# v1.net
KiCad netlist of a schematic drawn in EAGLE
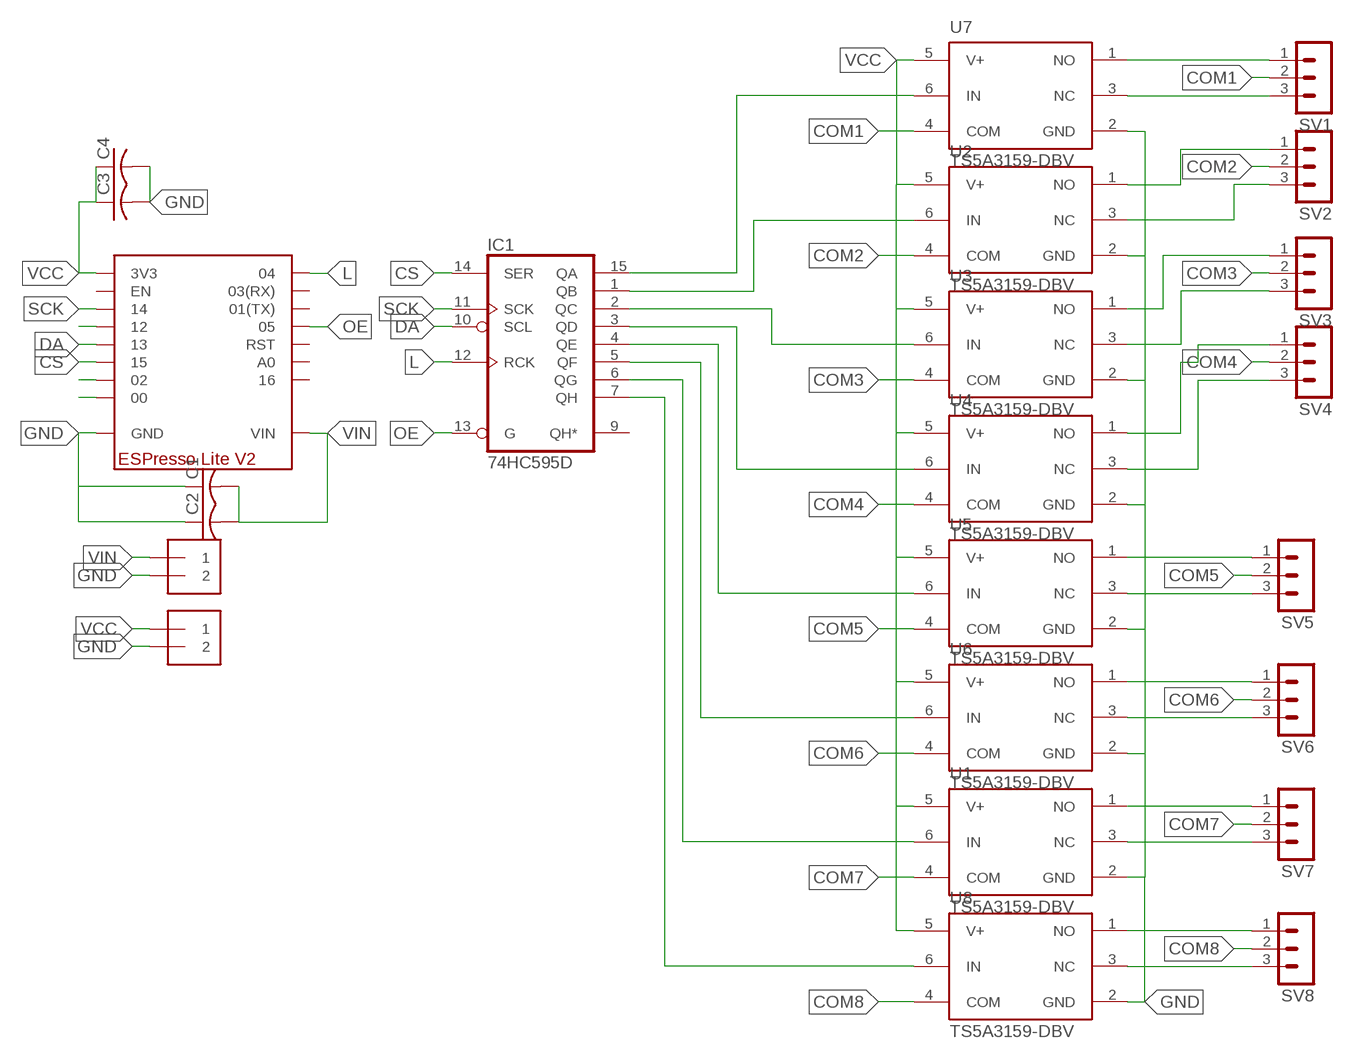
[diagram p0: schematic, sheet 1]

(export (version "E")
  (design (tool "Eeschema 10.0.6"))
  (components
    (comp (ref "C1")
      (value "C-USC0805")
      (footprint "eagle-import:C0805")
      (libsource (lib "eagle-import") (part "C-USC0805"))
    )
    (comp (ref "C2")
      (value "C-USC0805")
      (footprint "eagle-import:C0805")
      (libsource (lib "eagle-import") (part "C-USC0805"))
    )
    (comp (ref "C3")
      (value "C-USC0805")
      (footprint "eagle-import:C0805")
      (libsource (lib "eagle-import") (part "C-USC0805"))
    )
    (comp (ref "C4")
      (value "C-USC0805")
      (footprint "eagle-import:C0805")
      (libsource (lib "eagle-import") (part "C-USC0805"))
    )
    (comp (ref "IC1")
      (value "74HC595D")
      (footprint "eagle-import:SO16")
      (libsource (lib "eagle-import") (part "74595DHC"))
    )
    (comp (ref "J1")
      (value "1X2-3.5MM")
      (footprint "eagle-import:1X2-3.5MM")
      (libsource (lib "eagle-import") (part "1X2-3.5MM"))
    )
    (comp (ref "J2")
      (value "1X2-3.5MM")
      (footprint "eagle-import:1X2-3.5MM")
      (libsource (lib "eagle-import") (part "1X2-3.5MM"))
    )
    (comp (ref "SV1")
      (value "MA03-1")
      (footprint "eagle-import:MA03-1")
      (libsource (lib "eagle-import") (part "MA03-1"))
    )
    (comp (ref "SV2")
      (value "MA03-1")
      (footprint "eagle-import:MA03-1")
      (libsource (lib "eagle-import") (part "MA03-1"))
    )
    (comp (ref "SV3")
      (value "MA03-1")
      (footprint "eagle-import:MA03-1")
      (libsource (lib "eagle-import") (part "MA03-1"))
    )
    (comp (ref "SV4")
      (value "MA03-1")
      (footprint "eagle-import:MA03-1")
      (libsource (lib "eagle-import") (part "MA03-1"))
    )
    (comp (ref "SV5")
      (value "MA03-1")
      (footprint "eagle-import:MA03-1")
      (libsource (lib "eagle-import") (part "MA03-1"))
    )
    (comp (ref "SV6")
      (value "MA03-1")
      (footprint "eagle-import:MA03-1")
      (libsource (lib "eagle-import") (part "MA03-1"))
    )
    (comp (ref "SV7")
      (value "MA03-1")
      (footprint "eagle-import:MA03-1")
      (libsource (lib "eagle-import") (part "MA03-1"))
    )
    (comp (ref "SV8")
      (value "MA03-1")
      (footprint "eagle-import:MA03-1")
      (libsource (lib "eagle-import") (part "MA03-1"))
    )
    (comp (ref "U$1")
      (value "ESPRESSO-LITE-V2")
      (footprint "eagle-import:ESPRESSO-LITE-V2")
      (libsource (lib "eagle-import") (part "ESPRESSO-LITE-V2"))
    )
    (comp (ref "U1")
      (value "TS5A3159-DBV")
      (footprint "eagle-import:SOT23-6L")
      (libsource (lib "eagle-import") (part "TS5A3159-DBV"))
    )
    (comp (ref "U2")
      (value "TS5A3159-DBV")
      (footprint "eagle-import:SOT23-6L")
      (libsource (lib "eagle-import") (part "TS5A3159-DBV"))
    )
    (comp (ref "U3")
      (value "TS5A3159-DBV")
      (footprint "eagle-import:SOT23-6L")
      (libsource (lib "eagle-import") (part "TS5A3159-DBV"))
    )
    (comp (ref "U4")
      (value "TS5A3159-DBV")
      (footprint "eagle-import:SOT23-6L")
      (libsource (lib "eagle-import") (part "TS5A3159-DBV"))
    )
    (comp (ref "U5")
      (value "TS5A3159-DBV")
      (footprint "eagle-import:SOT23-6L")
      (libsource (lib "eagle-import") (part "TS5A3159-DBV"))
    )
    (comp (ref "U6")
      (value "TS5A3159-DBV")
      (footprint "eagle-import:SOT23-6L")
      (libsource (lib "eagle-import") (part "TS5A3159-DBV"))
    )
    (comp (ref "U7")
      (value "TS5A3159-DBV")
      (footprint "eagle-import:SOT23-6L")
      (libsource (lib "eagle-import") (part "TS5A3159-DBV"))
    )
    (comp (ref "U8")
      (value "TS5A3159-DBV")
      (footprint "eagle-import:SOT23-6L")
      (libsource (lib "eagle-import") (part "TS5A3159-DBV"))
    )
  )
  (nets
    (net (code "1") (name "COM1") (class "Default")
      (node (ref "SV1") (pin "2") (pinfunction "2_2") (pintype "passive"))
      (node (ref "U7") (pin "4") (pinfunction "COM_4") (pintype "bidirectional"))
    )
    (net (code "2") (name "COM2") (class "Default")
      (node (ref "SV2") (pin "2") (pinfunction "2_2") (pintype "passive"))
      (node (ref "U2") (pin "4") (pinfunction "COM_4") (pintype "bidirectional"))
    )
    (net (code "3") (name "COM3") (class "Default")
      (node (ref "SV3") (pin "2") (pinfunction "2_2") (pintype "passive"))
      (node (ref "U3") (pin "4") (pinfunction "COM_4") (pintype "bidirectional"))
    )
    (net (code "4") (name "COM4") (class "Default")
      (node (ref "SV4") (pin "2") (pinfunction "2_2") (pintype "passive"))
      (node (ref "U4") (pin "4") (pinfunction "COM_4") (pintype "bidirectional"))
    )
    (net (code "5") (name "COM5") (class "Default")
      (node (ref "SV5") (pin "2") (pinfunction "2_2") (pintype "passive"))
      (node (ref "U5") (pin "4") (pinfunction "COM_4") (pintype "bidirectional"))
    )
    (net (code "6") (name "COM6") (class "Default")
      (node (ref "SV6") (pin "2") (pinfunction "2_2") (pintype "passive"))
      (node (ref "U6") (pin "4") (pinfunction "COM_4") (pintype "bidirectional"))
    )
    (net (code "7") (name "COM7") (class "Default")
      (node (ref "SV7") (pin "2") (pinfunction "2_2") (pintype "passive"))
      (node (ref "U1") (pin "4") (pinfunction "COM_4") (pintype "bidirectional"))
    )
    (net (code "8") (name "COM8") (class "Default")
      (node (ref "SV8") (pin "2") (pinfunction "2_2") (pintype "passive"))
      (node (ref "U8") (pin "4") (pinfunction "COM_4") (pintype "bidirectional"))
    )
    (net (code "9") (name "CS") (class "Default")
      (node (ref "IC1") (pin "14") (pinfunction "SER_14") (pintype "input"))
      (node (ref "U$1") (pin "15") (pinfunction "15_15") (pintype "bidirectional"))
    )
    (net (code "10") (name "DA") (class "Default")
      (node (ref "IC1") (pin "10") (pinfunction "SCL_10") (pintype "input"))
      (node (ref "U$1") (pin "13") (pinfunction "13_13") (pintype "bidirectional"))
    )
    (net (code "11") (name "GND") (class "Default")
      (node (ref "C1") (pin "1") (pinfunction "1_1") (pintype "passive"))
      (node (ref "C2") (pin "1") (pinfunction "1_1") (pintype "passive"))
      (node (ref "C3") (pin "2") (pinfunction "2_2") (pintype "passive"))
      (node (ref "C4") (pin "2") (pinfunction "2_2") (pintype "passive"))
      (node (ref "J1") (pin "2") (pinfunction "2_2") (pintype "passive"))
      (node (ref "J2") (pin "2") (pinfunction "2_2") (pintype "passive"))
      (node (ref "U$1") (pin "GND1") (pinfunction "GND_GND1") (pintype "bidirectional"))
      (node (ref "U$1") (pin "GND2") (pinfunction "GND_GND2") (pintype "bidirectional"))
      (node (ref "U$1") (pin "GND3") (pinfunction "GND_GND3") (pintype "bidirectional"))
      (node (ref "U1") (pin "2") (pinfunction "GND_2") (pintype "power_in"))
      (node (ref "U2") (pin "2") (pinfunction "GND_2") (pintype "power_in"))
      (node (ref "U3") (pin "2") (pinfunction "GND_2") (pintype "power_in"))
      (node (ref "U4") (pin "2") (pinfunction "GND_2") (pintype "power_in"))
      (node (ref "U5") (pin "2") (pinfunction "GND_2") (pintype "power_in"))
      (node (ref "U6") (pin "2") (pinfunction "GND_2") (pintype "power_in"))
      (node (ref "U7") (pin "2") (pinfunction "GND_2") (pintype "power_in"))
      (node (ref "U8") (pin "2") (pinfunction "GND_2") (pintype "power_in"))
    )
    (net (code "12") (name "L") (class "Default")
      (node (ref "IC1") (pin "12") (pinfunction "RCK_12") (pintype "input"))
      (node (ref "U$1") (pin "04") (pinfunction "04_04") (pintype "bidirectional"))
    )
    (net (code "13") (name "Net-(IC1A-QA)") (class "Default")
      (node (ref "IC1") (pin "15") (pinfunction "QA_15") (pintype "tri_state"))
      (node (ref "U7") (pin "6") (pinfunction "IN_6") (pintype "input"))
    )
    (net (code "14") (name "Net-(IC1A-QB)") (class "Default")
      (node (ref "IC1") (pin "1") (pinfunction "QB_1") (pintype "tri_state"))
      (node (ref "U2") (pin "6") (pinfunction "IN_6") (pintype "input"))
    )
    (net (code "15") (name "Net-(IC1A-QC)") (class "Default")
      (node (ref "IC1") (pin "2") (pinfunction "QC_2") (pintype "tri_state"))
      (node (ref "U3") (pin "6") (pinfunction "IN_6") (pintype "input"))
    )
    (net (code "16") (name "Net-(IC1A-QD)") (class "Default")
      (node (ref "IC1") (pin "3") (pinfunction "QD_3") (pintype "tri_state"))
      (node (ref "U4") (pin "6") (pinfunction "IN_6") (pintype "input"))
    )
    (net (code "17") (name "Net-(IC1A-QE)") (class "Default")
      (node (ref "IC1") (pin "4") (pinfunction "QE_4") (pintype "tri_state"))
      (node (ref "U5") (pin "6") (pinfunction "IN_6") (pintype "input"))
    )
    (net (code "18") (name "Net-(IC1A-QF)") (class "Default")
      (node (ref "IC1") (pin "5") (pinfunction "QF_5") (pintype "tri_state"))
      (node (ref "U6") (pin "6") (pinfunction "IN_6") (pintype "input"))
    )
    (net (code "19") (name "Net-(IC1A-QG)") (class "Default")
      (node (ref "IC1") (pin "6") (pinfunction "QG_6") (pintype "tri_state"))
      (node (ref "U1") (pin "6") (pinfunction "IN_6") (pintype "input"))
    )
    (net (code "20") (name "Net-(IC1A-QH)") (class "Default")
      (node (ref "IC1") (pin "7") (pinfunction "QH_7") (pintype "tri_state"))
      (node (ref "U8") (pin "6") (pinfunction "IN_6") (pintype "input"))
    )
    (net (code "21") (name "Net-(U1-NC)") (class "Default")
      (node (ref "SV7") (pin "3") (pinfunction "3_3") (pintype "passive"))
      (node (ref "U1") (pin "3") (pinfunction "NC_3") (pintype "bidirectional"))
    )
    (net (code "22") (name "Net-(U1-NO)") (class "Default")
      (node (ref "SV7") (pin "1") (pinfunction "1_1") (pintype "passive"))
      (node (ref "U1") (pin "1") (pinfunction "NO_1") (pintype "bidirectional"))
    )
    (net (code "23") (name "Net-(U2-NC)") (class "Default")
      (node (ref "SV2") (pin "3") (pinfunction "3_3") (pintype "passive"))
      (node (ref "U2") (pin "3") (pinfunction "NC_3") (pintype "bidirectional"))
    )
    (net (code "24") (name "Net-(U2-NO)") (class "Default")
      (node (ref "SV2") (pin "1") (pinfunction "1_1") (pintype "passive"))
      (node (ref "U2") (pin "1") (pinfunction "NO_1") (pintype "bidirectional"))
    )
    (net (code "25") (name "Net-(U3-NC)") (class "Default")
      (node (ref "SV3") (pin "3") (pinfunction "3_3") (pintype "passive"))
      (node (ref "U3") (pin "3") (pinfunction "NC_3") (pintype "bidirectional"))
    )
    (net (code "26") (name "Net-(U3-NO)") (class "Default")
      (node (ref "SV3") (pin "1") (pinfunction "1_1") (pintype "passive"))
      (node (ref "U3") (pin "1") (pinfunction "NO_1") (pintype "bidirectional"))
    )
    (net (code "27") (name "Net-(U4-NC)") (class "Default")
      (node (ref "SV4") (pin "3") (pinfunction "3_3") (pintype "passive"))
      (node (ref "U4") (pin "3") (pinfunction "NC_3") (pintype "bidirectional"))
    )
    (net (code "28") (name "Net-(U4-NO)") (class "Default")
      (node (ref "SV4") (pin "1") (pinfunction "1_1") (pintype "passive"))
      (node (ref "U4") (pin "1") (pinfunction "NO_1") (pintype "bidirectional"))
    )
    (net (code "29") (name "Net-(U5-NC)") (class "Default")
      (node (ref "SV5") (pin "3") (pinfunction "3_3") (pintype "passive"))
      (node (ref "U5") (pin "3") (pinfunction "NC_3") (pintype "bidirectional"))
    )
    (net (code "30") (name "Net-(U5-NO)") (class "Default")
      (node (ref "SV5") (pin "1") (pinfunction "1_1") (pintype "passive"))
      (node (ref "U5") (pin "1") (pinfunction "NO_1") (pintype "bidirectional"))
    )
    (net (code "31") (name "Net-(U6-NC)") (class "Default")
      (node (ref "SV6") (pin "3") (pinfunction "3_3") (pintype "passive"))
      (node (ref "U6") (pin "3") (pinfunction "NC_3") (pintype "bidirectional"))
    )
    (net (code "32") (name "Net-(U6-NO)") (class "Default")
      (node (ref "SV6") (pin "1") (pinfunction "1_1") (pintype "passive"))
      (node (ref "U6") (pin "1") (pinfunction "NO_1") (pintype "bidirectional"))
    )
    (net (code "33") (name "Net-(U7-NC)") (class "Default")
      (node (ref "SV1") (pin "3") (pinfunction "3_3") (pintype "passive"))
      (node (ref "U7") (pin "3") (pinfunction "NC_3") (pintype "bidirectional"))
    )
    (net (code "34") (name "Net-(U7-NO)") (class "Default")
      (node (ref "SV1") (pin "1") (pinfunction "1_1") (pintype "passive"))
      (node (ref "U7") (pin "1") (pinfunction "NO_1") (pintype "bidirectional"))
    )
    (net (code "35") (name "Net-(U8-NC)") (class "Default")
      (node (ref "SV8") (pin "3") (pinfunction "3_3") (pintype "passive"))
      (node (ref "U8") (pin "3") (pinfunction "NC_3") (pintype "bidirectional"))
    )
    (net (code "36") (name "Net-(U8-NO)") (class "Default")
      (node (ref "SV8") (pin "1") (pinfunction "1_1") (pintype "passive"))
      (node (ref "U8") (pin "1") (pinfunction "NO_1") (pintype "bidirectional"))
    )
    (net (code "37") (name "OE") (class "Default")
      (node (ref "IC1") (pin "13") (pinfunction "G_13") (pintype "input"))
      (node (ref "U$1") (pin "05") (pinfunction "05_05") (pintype "bidirectional"))
    )
    (net (code "38") (name "SCK") (class "Default")
      (node (ref "IC1") (pin "11") (pinfunction "SCK_11") (pintype "input"))
      (node (ref "U$1") (pin "14") (pinfunction "14_14") (pintype "bidirectional"))
    )
    (net (code "39") (name "VCC") (class "Default")
      (node (ref "C3") (pin "1") (pinfunction "1_1") (pintype "passive"))
      (node (ref "C4") (pin "1") (pinfunction "1_1") (pintype "passive"))
      (node (ref "J2") (pin "1") (pinfunction "1_1") (pintype "passive"))
      (node (ref "U$1") (pin "3V3") (pinfunction "3V3_3V3") (pintype "bidirectional"))
      (node (ref "U1") (pin "5") (pinfunction "V+_5") (pintype "power_in"))
      (node (ref "U2") (pin "5") (pinfunction "V+_5") (pintype "power_in"))
      (node (ref "U3") (pin "5") (pinfunction "V+_5") (pintype "power_in"))
      (node (ref "U4") (pin "5") (pinfunction "V+_5") (pintype "power_in"))
      (node (ref "U5") (pin "5") (pinfunction "V+_5") (pintype "power_in"))
      (node (ref "U6") (pin "5") (pinfunction "V+_5") (pintype "power_in"))
      (node (ref "U7") (pin "5") (pinfunction "V+_5") (pintype "power_in"))
      (node (ref "U8") (pin "5") (pinfunction "V+_5") (pintype "power_in"))
    )
    (net (code "40") (name "VIN") (class "Default")
      (node (ref "C1") (pin "2") (pinfunction "2_2") (pintype "passive"))
      (node (ref "C2") (pin "2") (pinfunction "2_2") (pintype "passive"))
      (node (ref "J1") (pin "1") (pinfunction "1_1") (pintype "passive"))
      (node (ref "U$1") (pin "VIN1") (pinfunction "VIN_VIN1") (pintype "bidirectional"))
      (node (ref "U$1") (pin "VIN2") (pinfunction "VIN_VIN2") (pintype "bidirectional"))
    )
    (net (code "41") (name "unconnected-(IC1A-QH*-Pad9)") (class "Default")
      (node (ref "IC1") (pin "9") (pinfunction "QH*_9") (pintype "tri_state"))
    )
    (net (code "42") (name "unconnected-(U$1-01(TX)-Pad01)") (class "Default")
      (node (ref "U$1") (pin "01") (pinfunction "01(TX)_01") (pintype "bidirectional"))
    )
    (net (code "43") (name "unconnected-(U$1-03(RX)-Pad03)") (class "Default")
      (node (ref "U$1") (pin "03") (pinfunction "03(RX)_03") (pintype "bidirectional"))
    )
    (net (code "44") (name "unconnected-(U$1-A0-PadAO)") (class "Default")
      (node (ref "U$1") (pin "AO") (pinfunction "A0_AO") (pintype "bidirectional"))
    )
    (net (code "45") (name "unconnected-(U$1-Pad00)") (class "Default")
      (node (ref "U$1") (pin "00") (pinfunction "00_00") (pintype "bidirectional"))
    )
    (net (code "46") (name "unconnected-(U$1-Pad02)") (class "Default")
      (node (ref "U$1") (pin "02") (pinfunction "02_02") (pintype "bidirectional"))
    )
    (net (code "47") (name "unconnected-(U$1-Pad12)") (class "Default")
      (node (ref "U$1") (pin "12") (pinfunction "12_12") (pintype "bidirectional"))
    )
    (net (code "48") (name "unconnected-(U$1-Pad16)") (class "Default")
      (node (ref "U$1") (pin "16") (pinfunction "16_16") (pintype "bidirectional"))
    )
    (net (code "49") (name "unconnected-(U$1-PadEN)") (class "Default")
      (node (ref "U$1") (pin "EN") (pinfunction "EN_EN") (pintype "bidirectional"))
    )
    (net (code "50") (name "unconnected-(U$1-PadRST)") (class "Default")
      (node (ref "U$1") (pin "RST") (pinfunction "RST_RST") (pintype "bidirectional"))
    )
  )
)
